# Patch-Panel.net
KiCad netlist of a schematic drawn in EAGLE
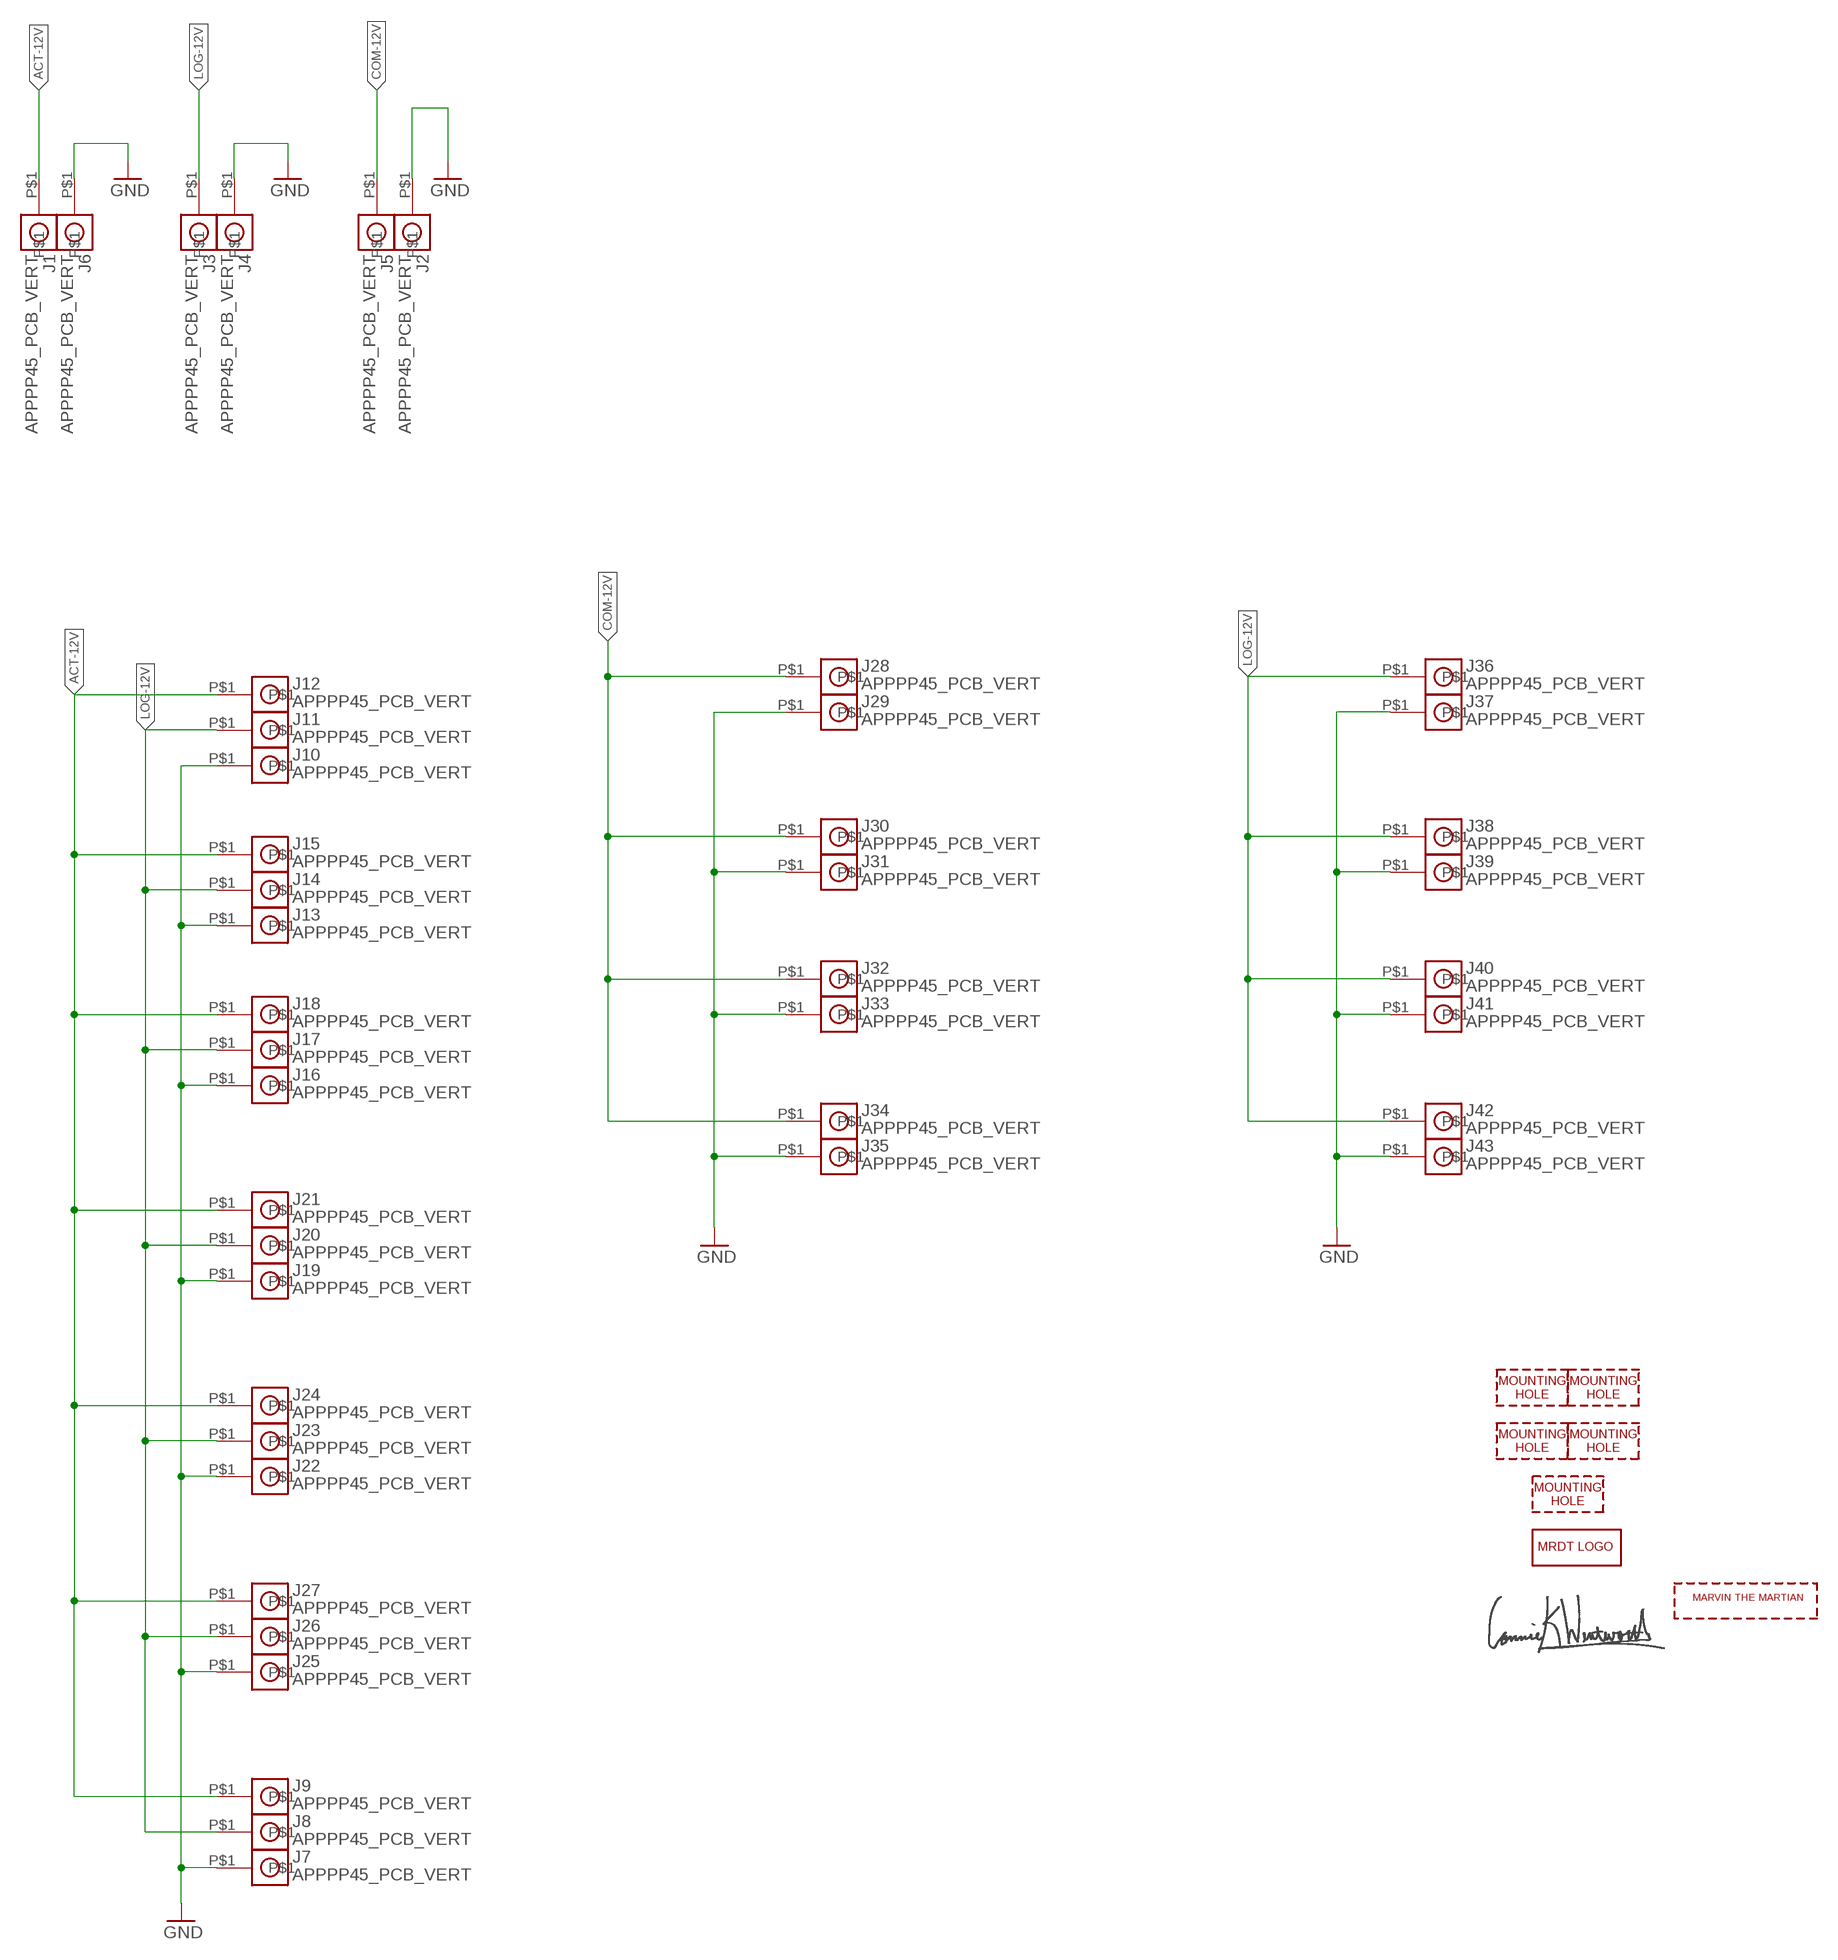
[diagram p0: schematic, sheet 1]

(export (version "E")
  (design (tool "Eeschema 10.0.6"))
  (components
    (comp (ref "H3")
      (value "MOUNTING_HOLE#6")
      (footprint "eagle-import:#6_SCREW")
      (libsource (lib "eagle-import") (part "MOUNTING_HOLE#6"))
    )
    (comp (ref "H4")
      (value "MOUNTING_HOLE#6")
      (footprint "eagle-import:#6_SCREW")
      (libsource (lib "eagle-import") (part "MOUNTING_HOLE#6"))
    )
    (comp (ref "H5")
      (value "MOUNTING_HOLE#6")
      (footprint "eagle-import:#6_SCREW")
      (libsource (lib "eagle-import") (part "MOUNTING_HOLE#6"))
    )
    (comp (ref "H6")
      (value "MOUNTING_HOLE#6")
      (footprint "eagle-import:#6_SCREW")
      (libsource (lib "eagle-import") (part "MOUNTING_HOLE#6"))
    )
    (comp (ref "H7")
      (value "MOUNTING_HOLE#6")
      (footprint "eagle-import:#6_SCREW")
      (libsource (lib "eagle-import") (part "MOUNTING_HOLE#6"))
    )
    (comp (ref "J1")
      (value "APPPP45_PCB_VERT")
      (footprint "eagle-import:APP45_PCB_VERT")
      (libsource (lib "eagle-import") (part "APPPP45_PCB_VERT"))
    )
    (comp (ref "J2")
      (value "APPPP45_PCB_VERT")
      (footprint "eagle-import:APP45_PCB_VERT")
      (libsource (lib "eagle-import") (part "APPPP45_PCB_VERT"))
    )
    (comp (ref "J3")
      (value "APPPP45_PCB_VERT")
      (footprint "eagle-import:APP45_PCB_VERT")
      (libsource (lib "eagle-import") (part "APPPP45_PCB_VERT"))
    )
    (comp (ref "J4")
      (value "APPPP45_PCB_VERT")
      (footprint "eagle-import:APP45_PCB_VERT")
      (libsource (lib "eagle-import") (part "APPPP45_PCB_VERT"))
    )
    (comp (ref "J5")
      (value "APPPP45_PCB_VERT")
      (footprint "eagle-import:APP45_PCB_VERT")
      (libsource (lib "eagle-import") (part "APPPP45_PCB_VERT"))
    )
    (comp (ref "J6")
      (value "APPPP45_PCB_VERT")
      (footprint "eagle-import:APP45_PCB_VERT")
      (libsource (lib "eagle-import") (part "APPPP45_PCB_VERT"))
    )
    (comp (ref "J7")
      (value "APPPP45_PCB_VERT")
      (footprint "eagle-import:APP45_PCB_VERT")
      (libsource (lib "eagle-import") (part "APPPP45_PCB_VERT"))
    )
    (comp (ref "J8")
      (value "APPPP45_PCB_VERT")
      (footprint "eagle-import:APP45_PCB_VERT")
      (libsource (lib "eagle-import") (part "APPPP45_PCB_VERT"))
    )
    (comp (ref "J9")
      (value "APPPP45_PCB_VERT")
      (footprint "eagle-import:APP45_PCB_VERT")
      (libsource (lib "eagle-import") (part "APPPP45_PCB_VERT"))
    )
    (comp (ref "J10")
      (value "APPPP45_PCB_VERT")
      (footprint "eagle-import:APP45_PCB_VERT")
      (libsource (lib "eagle-import") (part "APPPP45_PCB_VERT"))
    )
    (comp (ref "J11")
      (value "APPPP45_PCB_VERT")
      (footprint "eagle-import:APP45_PCB_VERT")
      (libsource (lib "eagle-import") (part "APPPP45_PCB_VERT"))
    )
    (comp (ref "J12")
      (value "APPPP45_PCB_VERT")
      (footprint "eagle-import:APP45_PCB_VERT")
      (libsource (lib "eagle-import") (part "APPPP45_PCB_VERT"))
    )
    (comp (ref "J13")
      (value "APPPP45_PCB_VERT")
      (footprint "eagle-import:APP45_PCB_VERT")
      (libsource (lib "eagle-import") (part "APPPP45_PCB_VERT"))
    )
    (comp (ref "J14")
      (value "APPPP45_PCB_VERT")
      (footprint "eagle-import:APP45_PCB_VERT")
      (libsource (lib "eagle-import") (part "APPPP45_PCB_VERT"))
    )
    (comp (ref "J15")
      (value "APPPP45_PCB_VERT")
      (footprint "eagle-import:APP45_PCB_VERT")
      (libsource (lib "eagle-import") (part "APPPP45_PCB_VERT"))
    )
    (comp (ref "J16")
      (value "APPPP45_PCB_VERT")
      (footprint "eagle-import:APP45_PCB_VERT")
      (libsource (lib "eagle-import") (part "APPPP45_PCB_VERT"))
    )
    (comp (ref "J17")
      (value "APPPP45_PCB_VERT")
      (footprint "eagle-import:APP45_PCB_VERT")
      (libsource (lib "eagle-import") (part "APPPP45_PCB_VERT"))
    )
    (comp (ref "J18")
      (value "APPPP45_PCB_VERT")
      (footprint "eagle-import:APP45_PCB_VERT")
      (libsource (lib "eagle-import") (part "APPPP45_PCB_VERT"))
    )
    (comp (ref "J19")
      (value "APPPP45_PCB_VERT")
      (footprint "eagle-import:APP45_PCB_VERT")
      (libsource (lib "eagle-import") (part "APPPP45_PCB_VERT"))
    )
    (comp (ref "J20")
      (value "APPPP45_PCB_VERT")
      (footprint "eagle-import:APP45_PCB_VERT")
      (libsource (lib "eagle-import") (part "APPPP45_PCB_VERT"))
    )
    (comp (ref "J21")
      (value "APPPP45_PCB_VERT")
      (footprint "eagle-import:APP45_PCB_VERT")
      (libsource (lib "eagle-import") (part "APPPP45_PCB_VERT"))
    )
    (comp (ref "J22")
      (value "APPPP45_PCB_VERT")
      (footprint "eagle-import:APP45_PCB_VERT")
      (libsource (lib "eagle-import") (part "APPPP45_PCB_VERT"))
    )
    (comp (ref "J23")
      (value "APPPP45_PCB_VERT")
      (footprint "eagle-import:APP45_PCB_VERT")
      (libsource (lib "eagle-import") (part "APPPP45_PCB_VERT"))
    )
    (comp (ref "J24")
      (value "APPPP45_PCB_VERT")
      (footprint "eagle-import:APP45_PCB_VERT")
      (libsource (lib "eagle-import") (part "APPPP45_PCB_VERT"))
    )
    (comp (ref "J25")
      (value "APPPP45_PCB_VERT")
      (footprint "eagle-import:APP45_PCB_VERT")
      (libsource (lib "eagle-import") (part "APPPP45_PCB_VERT"))
    )
    (comp (ref "J26")
      (value "APPPP45_PCB_VERT")
      (footprint "eagle-import:APP45_PCB_VERT")
      (libsource (lib "eagle-import") (part "APPPP45_PCB_VERT"))
    )
    (comp (ref "J27")
      (value "APPPP45_PCB_VERT")
      (footprint "eagle-import:APP45_PCB_VERT")
      (libsource (lib "eagle-import") (part "APPPP45_PCB_VERT"))
    )
    (comp (ref "J28")
      (value "APPPP45_PCB_VERT")
      (footprint "eagle-import:APP45_PCB_VERT")
      (libsource (lib "eagle-import") (part "APPPP45_PCB_VERT"))
    )
    (comp (ref "J29")
      (value "APPPP45_PCB_VERT")
      (footprint "eagle-import:APP45_PCB_VERT")
      (libsource (lib "eagle-import") (part "APPPP45_PCB_VERT"))
    )
    (comp (ref "J30")
      (value "APPPP45_PCB_VERT")
      (footprint "eagle-import:APP45_PCB_VERT")
      (libsource (lib "eagle-import") (part "APPPP45_PCB_VERT"))
    )
    (comp (ref "J31")
      (value "APPPP45_PCB_VERT")
      (footprint "eagle-import:APP45_PCB_VERT")
      (libsource (lib "eagle-import") (part "APPPP45_PCB_VERT"))
    )
    (comp (ref "J32")
      (value "APPPP45_PCB_VERT")
      (footprint "eagle-import:APP45_PCB_VERT")
      (libsource (lib "eagle-import") (part "APPPP45_PCB_VERT"))
    )
    (comp (ref "J33")
      (value "APPPP45_PCB_VERT")
      (footprint "eagle-import:APP45_PCB_VERT")
      (libsource (lib "eagle-import") (part "APPPP45_PCB_VERT"))
    )
    (comp (ref "J34")
      (value "APPPP45_PCB_VERT")
      (footprint "eagle-import:APP45_PCB_VERT")
      (libsource (lib "eagle-import") (part "APPPP45_PCB_VERT"))
    )
    (comp (ref "J35")
      (value "APPPP45_PCB_VERT")
      (footprint "eagle-import:APP45_PCB_VERT")
      (libsource (lib "eagle-import") (part "APPPP45_PCB_VERT"))
    )
    (comp (ref "J36")
      (value "APPPP45_PCB_VERT")
      (footprint "eagle-import:APP45_PCB_VERT")
      (libsource (lib "eagle-import") (part "APPPP45_PCB_VERT"))
    )
    (comp (ref "J37")
      (value "APPPP45_PCB_VERT")
      (footprint "eagle-import:APP45_PCB_VERT")
      (libsource (lib "eagle-import") (part "APPPP45_PCB_VERT"))
    )
    (comp (ref "J38")
      (value "APPPP45_PCB_VERT")
      (footprint "eagle-import:APP45_PCB_VERT")
      (libsource (lib "eagle-import") (part "APPPP45_PCB_VERT"))
    )
    (comp (ref "J39")
      (value "APPPP45_PCB_VERT")
      (footprint "eagle-import:APP45_PCB_VERT")
      (libsource (lib "eagle-import") (part "APPPP45_PCB_VERT"))
    )
    (comp (ref "J40")
      (value "APPPP45_PCB_VERT")
      (footprint "eagle-import:APP45_PCB_VERT")
      (libsource (lib "eagle-import") (part "APPPP45_PCB_VERT"))
    )
    (comp (ref "J41")
      (value "APPPP45_PCB_VERT")
      (footprint "eagle-import:APP45_PCB_VERT")
      (libsource (lib "eagle-import") (part "APPPP45_PCB_VERT"))
    )
    (comp (ref "J42")
      (value "APPPP45_PCB_VERT")
      (footprint "eagle-import:APP45_PCB_VERT")
      (libsource (lib "eagle-import") (part "APPPP45_PCB_VERT"))
    )
    (comp (ref "J43")
      (value "APPPP45_PCB_VERT")
      (footprint "eagle-import:APP45_PCB_VERT")
      (libsource (lib "eagle-import") (part "APPPP45_PCB_VERT"))
    )
    (comp (ref "LOGO1")
      (value "MRDT_LOGO")
      (footprint "eagle-import:MRDT_LOGO")
      (libsource (lib "eagle-import") (part "MRDT_LOGO"))
    )
    (comp (ref "U$1")
      (value "CONNIE_WENTWORTH_SIGNATURE")
      (footprint "eagle-import:CONNIE_WENTWORTH_SIGNATURE")
      (libsource (lib "eagle-import") (part "CONNIE_WENTWORTH_SIGNATURE"))
    )
    (comp (ref "U$2")
      (value "MARVIN-THE-MARTIAN")
      (footprint "eagle-import:MARVIN")
      (libsource (lib "eagle-import") (part "MARVIN-THE-MARTIAN"))
    )
  )
  (nets
    (net (code "1") (name "ACT-12V") (class "Default")
      (node (ref "J1") (pin "P$1") (pinfunction "P$1_P$1") (pintype "bidirectional"))
      (node (ref "J12") (pin "P$1") (pinfunction "P$1_P$1") (pintype "bidirectional"))
      (node (ref "J15") (pin "P$1") (pinfunction "P$1_P$1") (pintype "bidirectional"))
      (node (ref "J18") (pin "P$1") (pinfunction "P$1_P$1") (pintype "bidirectional"))
      (node (ref "J21") (pin "P$1") (pinfunction "P$1_P$1") (pintype "bidirectional"))
      (node (ref "J24") (pin "P$1") (pinfunction "P$1_P$1") (pintype "bidirectional"))
      (node (ref "J27") (pin "P$1") (pinfunction "P$1_P$1") (pintype "bidirectional"))
      (node (ref "J9") (pin "P$1") (pinfunction "P$1_P$1") (pintype "bidirectional"))
    )
    (net (code "2") (name "COM-12V") (class "Default")
      (node (ref "J28") (pin "P$1") (pinfunction "P$1_P$1") (pintype "bidirectional"))
      (node (ref "J30") (pin "P$1") (pinfunction "P$1_P$1") (pintype "bidirectional"))
      (node (ref "J32") (pin "P$1") (pinfunction "P$1_P$1") (pintype "bidirectional"))
      (node (ref "J34") (pin "P$1") (pinfunction "P$1_P$1") (pintype "bidirectional"))
      (node (ref "J5") (pin "P$1") (pinfunction "P$1_P$1") (pintype "bidirectional"))
    )
    (net (code "3") (name "GND") (class "Default")
      (node (ref "J10") (pin "P$1") (pinfunction "P$1_P$1") (pintype "bidirectional"))
      (node (ref "J13") (pin "P$1") (pinfunction "P$1_P$1") (pintype "bidirectional"))
      (node (ref "J16") (pin "P$1") (pinfunction "P$1_P$1") (pintype "bidirectional"))
      (node (ref "J19") (pin "P$1") (pinfunction "P$1_P$1") (pintype "bidirectional"))
      (node (ref "J2") (pin "P$1") (pinfunction "P$1_P$1") (pintype "bidirectional"))
      (node (ref "J22") (pin "P$1") (pinfunction "P$1_P$1") (pintype "bidirectional"))
      (node (ref "J25") (pin "P$1") (pinfunction "P$1_P$1") (pintype "bidirectional"))
      (node (ref "J29") (pin "P$1") (pinfunction "P$1_P$1") (pintype "bidirectional"))
      (node (ref "J31") (pin "P$1") (pinfunction "P$1_P$1") (pintype "bidirectional"))
      (node (ref "J33") (pin "P$1") (pinfunction "P$1_P$1") (pintype "bidirectional"))
      (node (ref "J35") (pin "P$1") (pinfunction "P$1_P$1") (pintype "bidirectional"))
      (node (ref "J37") (pin "P$1") (pinfunction "P$1_P$1") (pintype "bidirectional"))
      (node (ref "J39") (pin "P$1") (pinfunction "P$1_P$1") (pintype "bidirectional"))
      (node (ref "J4") (pin "P$1") (pinfunction "P$1_P$1") (pintype "bidirectional"))
      (node (ref "J41") (pin "P$1") (pinfunction "P$1_P$1") (pintype "bidirectional"))
      (node (ref "J43") (pin "P$1") (pinfunction "P$1_P$1") (pintype "bidirectional"))
      (node (ref "J6") (pin "P$1") (pinfunction "P$1_P$1") (pintype "bidirectional"))
      (node (ref "J7") (pin "P$1") (pinfunction "P$1_P$1") (pintype "bidirectional"))
    )
    (net (code "4") (name "LOG-12V") (class "Default")
      (node (ref "J11") (pin "P$1") (pinfunction "P$1_P$1") (pintype "bidirectional"))
      (node (ref "J14") (pin "P$1") (pinfunction "P$1_P$1") (pintype "bidirectional"))
      (node (ref "J17") (pin "P$1") (pinfunction "P$1_P$1") (pintype "bidirectional"))
      (node (ref "J20") (pin "P$1") (pinfunction "P$1_P$1") (pintype "bidirectional"))
      (node (ref "J23") (pin "P$1") (pinfunction "P$1_P$1") (pintype "bidirectional"))
      (node (ref "J26") (pin "P$1") (pinfunction "P$1_P$1") (pintype "bidirectional"))
      (node (ref "J3") (pin "P$1") (pinfunction "P$1_P$1") (pintype "bidirectional"))
      (node (ref "J36") (pin "P$1") (pinfunction "P$1_P$1") (pintype "bidirectional"))
      (node (ref "J38") (pin "P$1") (pinfunction "P$1_P$1") (pintype "bidirectional"))
      (node (ref "J40") (pin "P$1") (pinfunction "P$1_P$1") (pintype "bidirectional"))
      (node (ref "J42") (pin "P$1") (pinfunction "P$1_P$1") (pintype "bidirectional"))
      (node (ref "J8") (pin "P$1") (pinfunction "P$1_P$1") (pintype "bidirectional"))
    )
  )
)
